# Dicio.net
KiCad netlist of a schematic drawn in EAGLE
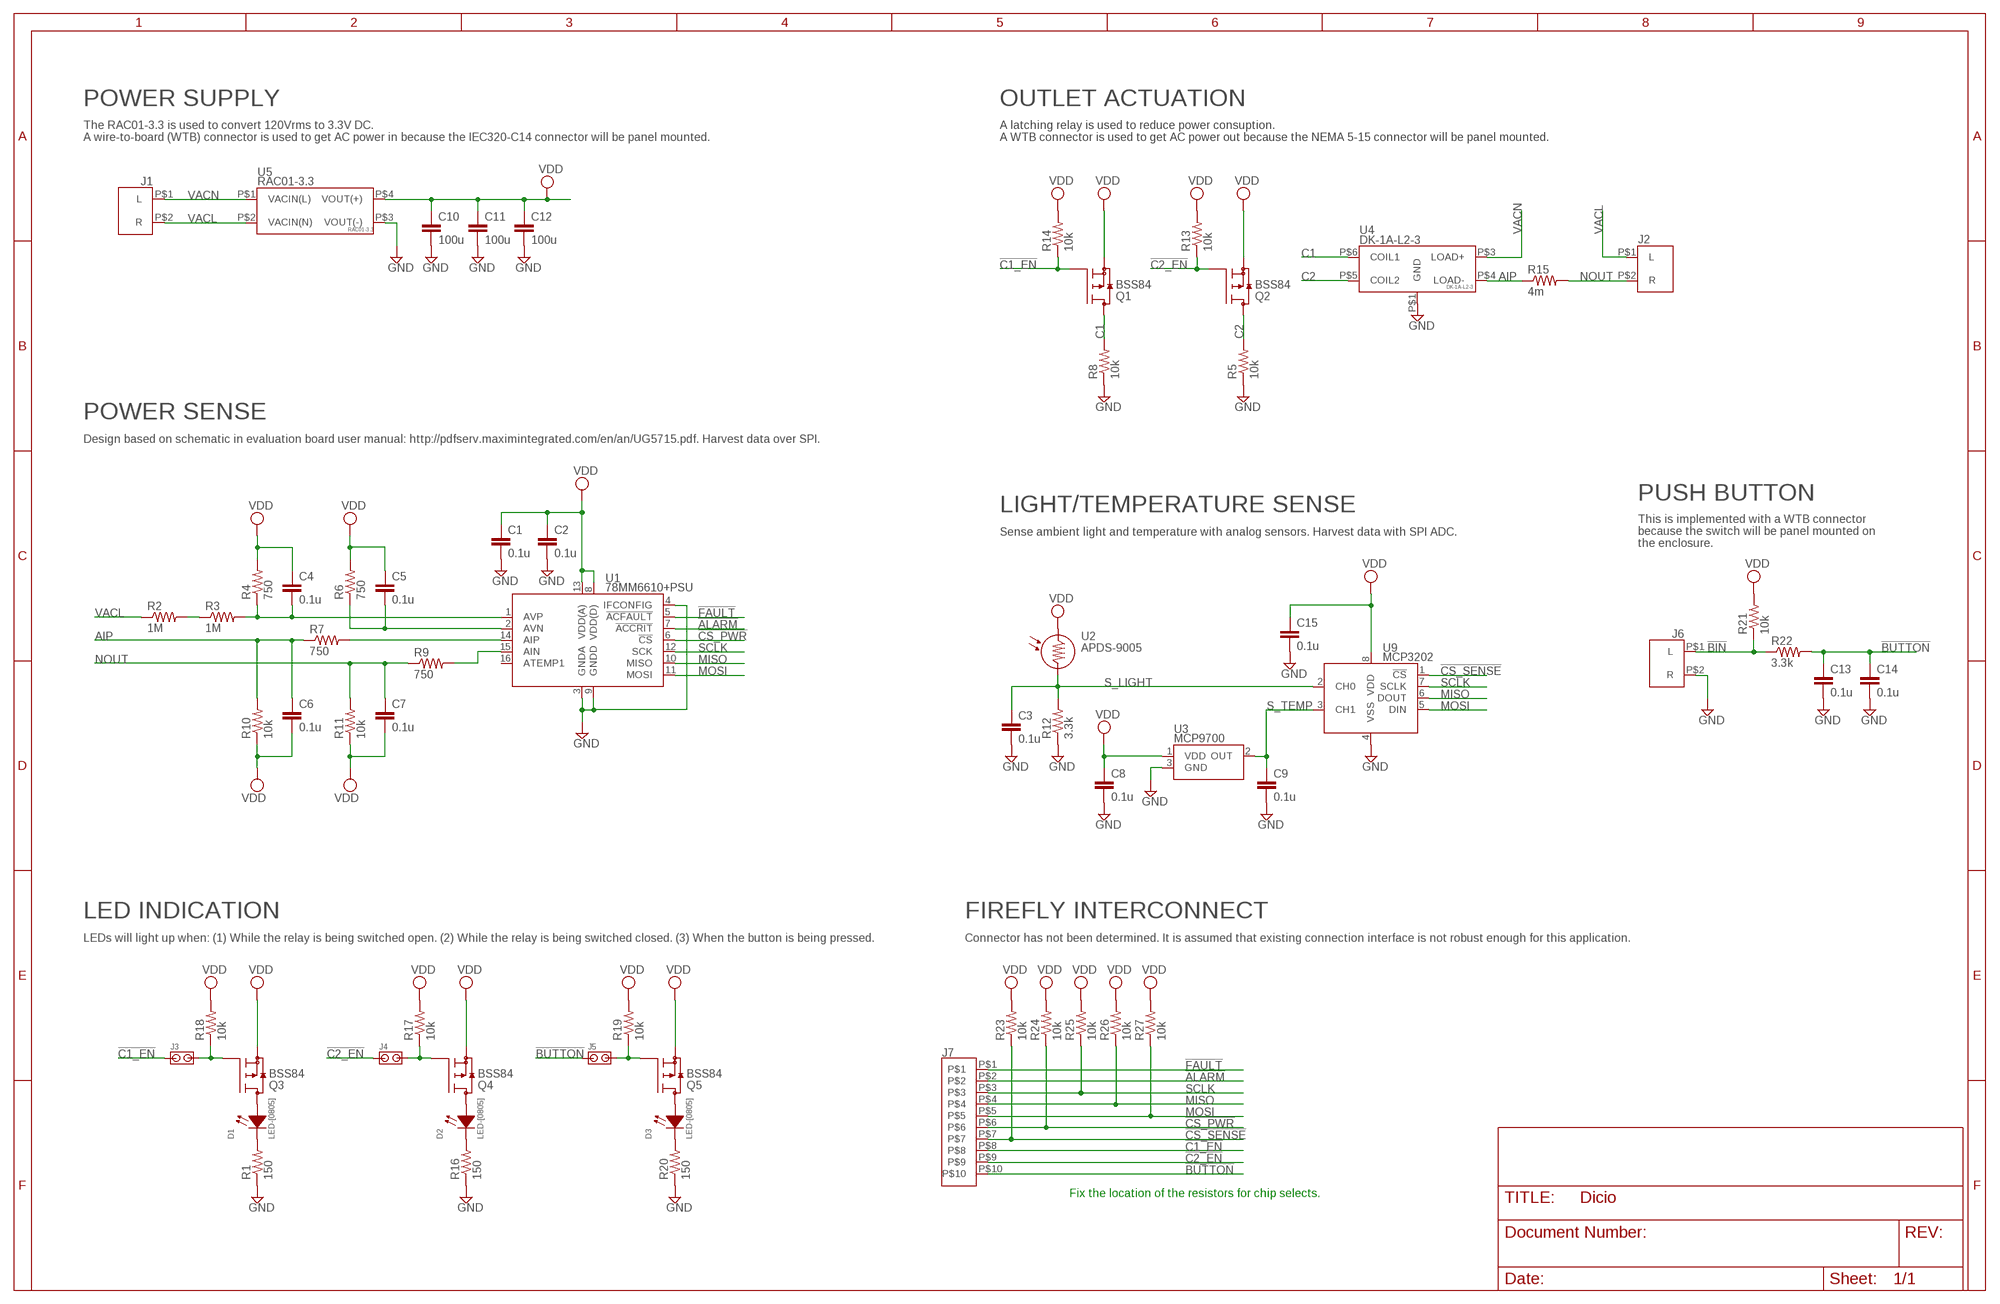
[diagram p0: schematic, sheet 1]

(export (version "E")
  (design (tool "Eeschema 10.0.6"))
  (components
    (comp (ref "C1")
      (value "0.1u")
      (footprint "eagle-import:C0805")
      (libsource (lib "eagle-import") (part "C-EUC0805"))
    )
    (comp (ref "C2")
      (value "0.1u")
      (footprint "eagle-import:C0805")
      (libsource (lib "eagle-import") (part "C-EUC0805"))
    )
    (comp (ref "C3")
      (value "0.1u")
      (footprint "eagle-import:C0805")
      (libsource (lib "eagle-import") (part "C-EUC0805"))
    )
    (comp (ref "C4")
      (value "0.1u")
      (footprint "eagle-import:C0805")
      (libsource (lib "eagle-import") (part "C-EUC0805"))
    )
    (comp (ref "C5")
      (value "0.1u")
      (footprint "eagle-import:C0805")
      (libsource (lib "eagle-import") (part "C-EUC0805"))
    )
    (comp (ref "C6")
      (value "0.1u")
      (footprint "eagle-import:C0805")
      (libsource (lib "eagle-import") (part "C-EUC0805"))
    )
    (comp (ref "C7")
      (value "0.1u")
      (footprint "eagle-import:C0805")
      (libsource (lib "eagle-import") (part "C-EUC0805"))
    )
    (comp (ref "C8")
      (value "0.1u")
      (footprint "eagle-import:C0805")
      (libsource (lib "eagle-import") (part "C-EUC0805"))
    )
    (comp (ref "C9")
      (value "0.1u")
      (footprint "eagle-import:C0805")
      (libsource (lib "eagle-import") (part "C-EUC0805"))
    )
    (comp (ref "C10")
      (value "100u")
      (footprint "eagle-import:C1206")
      (libsource (lib "eagle-import") (part "C-EUC1206"))
    )
    (comp (ref "C11")
      (value "100u")
      (footprint "eagle-import:C1206")
      (libsource (lib "eagle-import") (part "C-EUC1206"))
    )
    (comp (ref "C12")
      (value "100u")
      (footprint "eagle-import:C1206")
      (libsource (lib "eagle-import") (part "C-EUC1206"))
    )
    (comp (ref "C13")
      (value "0.1u")
      (footprint "eagle-import:C0805")
      (libsource (lib "eagle-import") (part "C-EUC0805"))
    )
    (comp (ref "C14")
      (value "0.1u")
      (footprint "eagle-import:C0805")
      (libsource (lib "eagle-import") (part "C-EUC0805"))
    )
    (comp (ref "C15")
      (value "0.1u")
      (footprint "eagle-import:C0805")
      (libsource (lib "eagle-import") (part "C-EUC0805"))
    )
    (comp (ref "D1")
      (value "LED-[0805]")
      (footprint "eagle-import:L0805")
      (libsource (lib "eagle-import") (part "LED-[0805]"))
    )
    (comp (ref "D2")
      (value "LED-[0805]")
      (footprint "eagle-import:L0805")
      (libsource (lib "eagle-import") (part "LED-[0805]"))
    )
    (comp (ref "D3")
      (value "LED-[0805]")
      (footprint "eagle-import:L0805")
      (libsource (lib "eagle-import") (part "LED-[0805]"))
    )
    (comp (ref "J1")
      (value "WTB-2")
      (footprint "eagle-import:[TERM][2][0.2]")
      (libsource (lib "eagle-import") (part "WTB-2"))
    )
    (comp (ref "J2")
      (value "WTB-2")
      (footprint "eagle-import:[TERM][2][0.2]")
      (libsource (lib "eagle-import") (part "WTB-2"))
    )
    (comp (ref "J3")
      (value "JMP2")
      (footprint "eagle-import:JMP2")
      (libsource (lib "eagle-import") (part "JMP2"))
    )
    (comp (ref "J4")
      (value "JMP2")
      (footprint "eagle-import:JMP2")
      (libsource (lib "eagle-import") (part "JMP2"))
    )
    (comp (ref "J5")
      (value "JMP2")
      (footprint "eagle-import:JMP2")
      (libsource (lib "eagle-import") (part "JMP2"))
    )
    (comp (ref "J6")
      (value "WTB-2")
      (footprint "eagle-import:[TERM][2][0.2]")
      (libsource (lib "eagle-import") (part "WTB-2"))
    )
    (comp (ref "J7")
      (value "TERM10")
      (footprint "eagle-import:TERM10")
      (libsource (lib "eagle-import") (part "TERM10"))
    )
    (comp (ref "Q1")
      (value "BSS84")
      (footprint "eagle-import:SOT23")
      (libsource (lib "eagle-import") (part "BSS84"))
    )
    (comp (ref "Q2")
      (value "BSS84")
      (footprint "eagle-import:SOT23")
      (libsource (lib "eagle-import") (part "BSS84"))
    )
    (comp (ref "Q3")
      (value "BSS84")
      (footprint "eagle-import:SOT23")
      (libsource (lib "eagle-import") (part "BSS84"))
    )
    (comp (ref "Q4")
      (value "BSS84")
      (footprint "eagle-import:SOT23")
      (libsource (lib "eagle-import") (part "BSS84"))
    )
    (comp (ref "Q5")
      (value "BSS84")
      (footprint "eagle-import:SOT23")
      (libsource (lib "eagle-import") (part "BSS84"))
    )
    (comp (ref "R1")
      (value "150")
      (footprint "eagle-import:R0805")
      (libsource (lib "eagle-import") (part "R-US_R0805"))
    )
    (comp (ref "R2")
      (value "1M")
      (footprint "eagle-import:R0805")
      (libsource (lib "eagle-import") (part "R-US_R0805"))
    )
    (comp (ref "R3")
      (value "1M")
      (footprint "eagle-import:R0805")
      (libsource (lib "eagle-import") (part "R-US_R0805"))
    )
    (comp (ref "R4")
      (value "750")
      (footprint "eagle-import:R0805")
      (libsource (lib "eagle-import") (part "R-US_R0805"))
    )
    (comp (ref "R5")
      (value "10k")
      (footprint "eagle-import:R0805")
      (libsource (lib "eagle-import") (part "R-US_R0805"))
    )
    (comp (ref "R6")
      (value "750")
      (footprint "eagle-import:R0805")
      (libsource (lib "eagle-import") (part "R-US_R0805"))
    )
    (comp (ref "R7")
      (value "750")
      (footprint "eagle-import:R0805")
      (libsource (lib "eagle-import") (part "R-US_R0805"))
    )
    (comp (ref "R8")
      (value "10k")
      (footprint "eagle-import:R0805")
      (libsource (lib "eagle-import") (part "R-US_R0805"))
    )
    (comp (ref "R9")
      (value "750")
      (footprint "eagle-import:R0805")
      (libsource (lib "eagle-import") (part "R-US_R0805"))
    )
    (comp (ref "R10")
      (value "10k")
      (footprint "eagle-import:R0805")
      (libsource (lib "eagle-import") (part "R-US_R0805"))
    )
    (comp (ref "R11")
      (value "10k")
      (footprint "eagle-import:R0805")
      (libsource (lib "eagle-import") (part "R-US_R0805"))
    )
    (comp (ref "R12")
      (value "3.3k")
      (footprint "eagle-import:R0805")
      (libsource (lib "eagle-import") (part "R-US_R0805"))
    )
    (comp (ref "R13")
      (value "10k")
      (footprint "eagle-import:R0805")
      (libsource (lib "eagle-import") (part "R-US_R0805"))
    )
    (comp (ref "R14")
      (value "10k")
      (footprint "eagle-import:R0805")
      (libsource (lib "eagle-import") (part "R-US_R0805"))
    )
    (comp (ref "R15")
      (value "4m")
      (footprint "eagle-import:R2512")
      (libsource (lib "eagle-import") (part "R-US_R2512"))
    )
    (comp (ref "R16")
      (value "150")
      (footprint "eagle-import:R0805")
      (libsource (lib "eagle-import") (part "R-US_R0805"))
    )
    (comp (ref "R17")
      (value "10k")
      (footprint "eagle-import:R0805")
      (libsource (lib "eagle-import") (part "R-US_R0805"))
    )
    (comp (ref "R18")
      (value "10k")
      (footprint "eagle-import:R0805")
      (libsource (lib "eagle-import") (part "R-US_R0805"))
    )
    (comp (ref "R19")
      (value "10k")
      (footprint "eagle-import:R0805")
      (libsource (lib "eagle-import") (part "R-US_R0805"))
    )
    (comp (ref "R20")
      (value "150")
      (footprint "eagle-import:R0805")
      (libsource (lib "eagle-import") (part "R-US_R0805"))
    )
    (comp (ref "R21")
      (value "10k")
      (footprint "eagle-import:R0805")
      (libsource (lib "eagle-import") (part "R-US_R0805"))
    )
    (comp (ref "R22")
      (value "3.3k")
      (footprint "eagle-import:R0805")
      (libsource (lib "eagle-import") (part "R-US_R0805"))
    )
    (comp (ref "R23")
      (value "10k")
      (footprint "eagle-import:R0805")
      (libsource (lib "eagle-import") (part "R-US_R0805"))
    )
    (comp (ref "R24")
      (value "10k")
      (footprint "eagle-import:R0805")
      (libsource (lib "eagle-import") (part "R-US_R0805"))
    )
    (comp (ref "R25")
      (value "10k")
      (footprint "eagle-import:R0805")
      (libsource (lib "eagle-import") (part "R-US_R0805"))
    )
    (comp (ref "R26")
      (value "10k")
      (footprint "eagle-import:R0805")
      (libsource (lib "eagle-import") (part "R-US_R0805"))
    )
    (comp (ref "R27")
      (value "10k")
      (footprint "eagle-import:R0805")
      (libsource (lib "eagle-import") (part "R-US_R0805"))
    )
    (comp (ref "U1")
      (value "78MM6610+PSU")
      (footprint "eagle-import:TSSOP16")
      (libsource (lib "eagle-import") (part "78MM6610+PSU"))
    )
    (comp (ref "U2")
      (value "APDS-9005")
      (footprint "eagle-import:APDS-9005")
      (libsource (lib "eagle-import") (part "APDS-9005"))
    )
    (comp (ref "U3")
      (value "MCP9700")
      (footprint "eagle-import:SOT23")
      (libsource (lib "eagle-import") (part "MCP9700"))
    )
    (comp (ref "U4")
      (value "DK-1A-L2-3")
      (footprint "eagle-import:DK-1A-L2-3")
      (libsource (lib "eagle-import") (part "DK-1A-L2-3"))
    )
    (comp (ref "U5")
      (value "RAC01-3.3")
      (footprint "eagle-import:RAC01-3.3")
      (libsource (lib "eagle-import") (part "RAC01-3.3"))
    )
    (comp (ref "U9")
      (value "MCP3202")
      (footprint "eagle-import:MSOP-8[MCP3202]")
      (libsource (lib "eagle-import") (part "MCP3202"))
    )
  )
  (nets
    (net (code "1") (name "/AIP") (class "Default")
      (node (ref "C6") (pin "1") (pinfunction "1_1") (pintype "passive"))
      (node (ref "R10") (pin "2") (pinfunction "2_2") (pintype "passive"))
      (node (ref "R15") (pin "1") (pinfunction "1_1") (pintype "passive"))
      (node (ref "R7") (pin "1") (pinfunction "1_1") (pintype "passive"))
      (node (ref "U4") (pin "P$4") (pinfunction "LOAD-_P$4") (pintype "bidirectional"))
    )
    (net (code "2") (name "/C1") (class "Default")
      (node (ref "Q1") (pin "3") (pinfunction "D_3") (pintype "bidirectional"))
      (node (ref "R8") (pin "2") (pinfunction "2_2") (pintype "passive"))
      (node (ref "U4") (pin "P$6") (pinfunction "COIL1_P$6") (pintype "bidirectional"))
    )
    (net (code "3") (name "/C2") (class "Default")
      (node (ref "Q2") (pin "3") (pinfunction "D_3") (pintype "bidirectional"))
      (node (ref "R5") (pin "2") (pinfunction "2_2") (pintype "passive"))
      (node (ref "U4") (pin "P$5") (pinfunction "COIL2_P$5") (pintype "bidirectional"))
    )
    (net (code "4") (name "/MISO") (class "Default")
      (node (ref "J7") (pin "P$4") (pinfunction "P$4_P$4") (pintype "bidirectional"))
      (node (ref "R26") (pin "1") (pinfunction "1_1") (pintype "passive"))
      (node (ref "U1") (pin "10") (pinfunction "MISO_10") (pintype "bidirectional"))
      (node (ref "U9") (pin "6") (pinfunction "DOUT_6") (pintype "bidirectional"))
    )
    (net (code "5") (name "/MOSI") (class "Default")
      (node (ref "J7") (pin "P$5") (pinfunction "P$5_P$5") (pintype "bidirectional"))
      (node (ref "R27") (pin "1") (pinfunction "1_1") (pintype "passive"))
      (node (ref "U1") (pin "11") (pinfunction "MOSI_11") (pintype "bidirectional"))
      (node (ref "U9") (pin "5") (pinfunction "DIN_5") (pintype "bidirectional"))
    )
    (net (code "6") (name "/NOUT") (class "Default")
      (node (ref "C7") (pin "1") (pinfunction "1_1") (pintype "passive"))
      (node (ref "J2") (pin "P$2") (pinfunction "R_P$2") (pintype "bidirectional"))
      (node (ref "R11") (pin "2") (pinfunction "2_2") (pintype "passive"))
      (node (ref "R15") (pin "2") (pinfunction "2_2") (pintype "passive"))
      (node (ref "R9") (pin "1") (pinfunction "1_1") (pintype "passive"))
    )
    (net (code "7") (name "/SCLK") (class "Default")
      (node (ref "J7") (pin "P$3") (pinfunction "P$3_P$3") (pintype "bidirectional"))
      (node (ref "R25") (pin "1") (pinfunction "1_1") (pintype "passive"))
      (node (ref "U1") (pin "12") (pinfunction "SCK_12") (pintype "bidirectional"))
      (node (ref "U9") (pin "7") (pinfunction "SCLK_7") (pintype "bidirectional"))
    )
    (net (code "8") (name "/S_LIGHT") (class "Default")
      (node (ref "C3") (pin "1") (pinfunction "1_1") (pintype "passive"))
      (node (ref "R12") (pin "2") (pinfunction "2_2") (pintype "passive"))
      (node (ref "U2") (pin "6") (pinfunction "ROUT_6") (pintype "bidirectional"))
      (node (ref "U9") (pin "2") (pinfunction "CH0_2") (pintype "bidirectional"))
    )
    (net (code "9") (name "/S_TEMP") (class "Default")
      (node (ref "C9") (pin "1") (pinfunction "1_1") (pintype "passive"))
      (node (ref "U3") (pin "2") (pinfunction "OUT_2") (pintype "bidirectional"))
      (node (ref "U9") (pin "3") (pinfunction "CH1_3") (pintype "bidirectional"))
    )
    (net (code "10") (name "/VACL") (class "Default")
      (node (ref "J1") (pin "P$2") (pinfunction "R_P$2") (pintype "bidirectional"))
      (node (ref "J2") (pin "P$1") (pinfunction "L_P$1") (pintype "bidirectional"))
      (node (ref "R2") (pin "1") (pinfunction "1_1") (pintype "passive"))
      (node (ref "U5") (pin "P$2") (pinfunction "VACIN(N)_P$2") (pintype "bidirectional"))
    )
    (net (code "11") (name "/VACN") (class "Default")
      (node (ref "J1") (pin "P$1") (pinfunction "L_P$1") (pintype "bidirectional"))
      (node (ref "U4") (pin "P$3") (pinfunction "LOAD+_P$3") (pintype "bidirectional"))
      (node (ref "U5") (pin "P$1") (pinfunction "VACIN(L)_P$1") (pintype "bidirectional"))
    )
    (net (code "12") (name "/~{ALARM}") (class "Default")
      (node (ref "J7") (pin "P$2") (pinfunction "P$2_P$2") (pintype "bidirectional"))
      (node (ref "U1") (pin "7") (pinfunction "~{ACCRIT}_7") (pintype "bidirectional"))
    )
    (net (code "13") (name "/~{BIN}") (class "Default")
      (node (ref "J6") (pin "P$1") (pinfunction "L_P$1") (pintype "bidirectional"))
      (node (ref "R21") (pin "1") (pinfunction "1_1") (pintype "passive"))
      (node (ref "R22") (pin "1") (pinfunction "1_1") (pintype "passive"))
    )
    (net (code "14") (name "/~{BUTTON}") (class "Default")
      (node (ref "C13") (pin "1") (pinfunction "1_1") (pintype "passive"))
      (node (ref "C14") (pin "1") (pinfunction "1_1") (pintype "passive"))
      (node (ref "J5") (pin "P$2") (pinfunction "P$2_P$2") (pintype "bidirectional"))
      (node (ref "J7") (pin "P$10") (pinfunction "P$10_P$10") (pintype "bidirectional"))
      (node (ref "R22") (pin "2") (pinfunction "2_2") (pintype "passive"))
    )
    (net (code "15") (name "/~{C1_EN}") (class "Default")
      (node (ref "J3") (pin "P$2") (pinfunction "P$2_P$2") (pintype "bidirectional"))
      (node (ref "J7") (pin "P$8") (pinfunction "P$8_P$8") (pintype "bidirectional"))
      (node (ref "Q1") (pin "1") (pinfunction "G_1") (pintype "bidirectional"))
      (node (ref "R14") (pin "1") (pinfunction "1_1") (pintype "passive"))
    )
    (net (code "16") (name "/~{C2_EN}") (class "Default")
      (node (ref "J4") (pin "P$2") (pinfunction "P$2_P$2") (pintype "bidirectional"))
      (node (ref "J7") (pin "P$9") (pinfunction "P$9_P$9") (pintype "bidirectional"))
      (node (ref "Q2") (pin "1") (pinfunction "G_1") (pintype "bidirectional"))
      (node (ref "R13") (pin "1") (pinfunction "1_1") (pintype "passive"))
    )
    (net (code "17") (name "/~{CS_PWR}") (class "Default")
      (node (ref "J7") (pin "P$6") (pinfunction "P$6_P$6") (pintype "bidirectional"))
      (node (ref "R24") (pin "1") (pinfunction "1_1") (pintype "passive"))
      (node (ref "U1") (pin "6") (pinfunction "~{CS}_6") (pintype "bidirectional"))
    )
    (net (code "18") (name "/~{CS_SENSE}") (class "Default")
      (node (ref "J7") (pin "P$7") (pinfunction "P$7_P$7") (pintype "bidirectional"))
      (node (ref "R23") (pin "1") (pinfunction "1_1") (pintype "passive"))
      (node (ref "U9") (pin "1") (pinfunction "~{CS}_1") (pintype "bidirectional"))
    )
    (net (code "19") (name "/~{FAULT}") (class "Default")
      (node (ref "J7") (pin "P$1") (pinfunction "P$1_P$1") (pintype "bidirectional"))
      (node (ref "U1") (pin "5") (pinfunction "~{ACFAULT}_5") (pintype "bidirectional"))
    )
    (net (code "20") (name "GND") (class "Default")
      (node (ref "C1") (pin "2") (pinfunction "2_2") (pintype "passive"))
      (node (ref "C10") (pin "2") (pinfunction "2_2") (pintype "passive"))
      (node (ref "C11") (pin "2") (pinfunction "2_2") (pintype "passive"))
      (node (ref "C12") (pin "2") (pinfunction "2_2") (pintype "passive"))
      (node (ref "C13") (pin "2") (pinfunction "2_2") (pintype "passive"))
      (node (ref "C14") (pin "2") (pinfunction "2_2") (pintype "passive"))
      (node (ref "C15") (pin "2") (pinfunction "2_2") (pintype "passive"))
      (node (ref "C2") (pin "2") (pinfunction "2_2") (pintype "passive"))
      (node (ref "C3") (pin "2") (pinfunction "2_2") (pintype "passive"))
      (node (ref "C8") (pin "2") (pinfunction "2_2") (pintype "passive"))
      (node (ref "C9") (pin "2") (pinfunction "2_2") (pintype "passive"))
      (node (ref "J6") (pin "P$2") (pinfunction "R_P$2") (pintype "bidirectional"))
      (node (ref "R1") (pin "1") (pinfunction "1_1") (pintype "passive"))
      (node (ref "R12") (pin "1") (pinfunction "1_1") (pintype "passive"))
      (node (ref "R16") (pin "1") (pinfunction "1_1") (pintype "passive"))
      (node (ref "R20") (pin "1") (pinfunction "1_1") (pintype "passive"))
      (node (ref "R5") (pin "1") (pinfunction "1_1") (pintype "passive"))
      (node (ref "R8") (pin "1") (pinfunction "1_1") (pintype "passive"))
      (node (ref "U1") (pin "3") (pinfunction "GNDA_3") (pintype "bidirectional"))
      (node (ref "U1") (pin "4") (pinfunction "IFCONFIG_4") (pintype "bidirectional"))
      (node (ref "U1") (pin "9") (pinfunction "GNDD_9") (pintype "bidirectional"))
      (node (ref "U3") (pin "3") (pinfunction "GND_3") (pintype "bidirectional"))
      (node (ref "U4") (pin "P$1") (pinfunction "GND_P$1") (pintype "bidirectional"))
      (node (ref "U5") (pin "P$3") (pinfunction "VOUT(-)_P$3") (pintype "bidirectional"))
      (node (ref "U9") (pin "4") (pinfunction "VSS_4") (pintype "bidirectional"))
    )
    (net (code "21") (name "Net-(D1-A)") (class "Default")
      (node (ref "D1") (pin "1") (pinfunction "A_1") (pintype "bidirectional"))
      (node (ref "Q3") (pin "3") (pinfunction "D_3") (pintype "bidirectional"))
    )
    (net (code "22") (name "Net-(D1-C)") (class "Default")
      (node (ref "D1") (pin "2") (pinfunction "C_2") (pintype "bidirectional"))
      (node (ref "R1") (pin "2") (pinfunction "2_2") (pintype "passive"))
    )
    (net (code "23") (name "Net-(D2-A)") (class "Default")
      (node (ref "D2") (pin "1") (pinfunction "A_1") (pintype "bidirectional"))
      (node (ref "Q4") (pin "3") (pinfunction "D_3") (pintype "bidirectional"))
    )
    (net (code "24") (name "Net-(D2-C)") (class "Default")
      (node (ref "D2") (pin "2") (pinfunction "C_2") (pintype "bidirectional"))
      (node (ref "R16") (pin "2") (pinfunction "2_2") (pintype "passive"))
    )
    (net (code "25") (name "Net-(D3-A)") (class "Default")
      (node (ref "D3") (pin "1") (pinfunction "A_1") (pintype "bidirectional"))
      (node (ref "Q5") (pin "3") (pinfunction "D_3") (pintype "bidirectional"))
    )
    (net (code "26") (name "Net-(D3-C)") (class "Default")
      (node (ref "D3") (pin "2") (pinfunction "C_2") (pintype "bidirectional"))
      (node (ref "R20") (pin "2") (pinfunction "2_2") (pintype "passive"))
    )
    (net (code "27") (name "Net-(J3-1)") (class "Default")
      (node (ref "J3") (pin "P$1") (pinfunction "1_P$1") (pintype "bidirectional"))
      (node (ref "Q3") (pin "1") (pinfunction "G_1") (pintype "bidirectional"))
      (node (ref "R18") (pin "1") (pinfunction "1_1") (pintype "passive"))
    )
    (net (code "28") (name "Net-(J4-1)") (class "Default")
      (node (ref "J4") (pin "P$1") (pinfunction "1_P$1") (pintype "bidirectional"))
      (node (ref "Q4") (pin "1") (pinfunction "G_1") (pintype "bidirectional"))
      (node (ref "R17") (pin "1") (pinfunction "1_1") (pintype "passive"))
    )
    (net (code "29") (name "Net-(J5-1)") (class "Default")
      (node (ref "J5") (pin "P$1") (pinfunction "1_P$1") (pintype "bidirectional"))
      (node (ref "Q5") (pin "1") (pinfunction "G_1") (pintype "bidirectional"))
      (node (ref "R19") (pin "1") (pinfunction "1_1") (pintype "passive"))
    )
    (net (code "30") (name "Net-(R2-Pad2)") (class "Default")
      (node (ref "R2") (pin "2") (pinfunction "2_2") (pintype "passive"))
      (node (ref "R3") (pin "1") (pinfunction "1_1") (pintype "passive"))
    )
    (net (code "31") (name "Net-(U1-AIN)") (class "Default")
      (node (ref "R9") (pin "2") (pinfunction "2_2") (pintype "passive"))
      (node (ref "U1") (pin "15") (pinfunction "AIN_15") (pintype "bidirectional"))
    )
    (net (code "32") (name "Net-(U1-AIP)") (class "Default")
      (node (ref "R7") (pin "2") (pinfunction "2_2") (pintype "passive"))
      (node (ref "U1") (pin "14") (pinfunction "AIP_14") (pintype "bidirectional"))
    )
    (net (code "33") (name "Net-(U1-AVN)") (class "Default")
      (node (ref "C5") (pin "2") (pinfunction "2_2") (pintype "passive"))
      (node (ref "R6") (pin "1") (pinfunction "1_1") (pintype "passive"))
      (node (ref "U1") (pin "2") (pinfunction "AVN_2") (pintype "bidirectional"))
    )
    (net (code "34") (name "Net-(U1-AVP)") (class "Default")
      (node (ref "C4") (pin "2") (pinfunction "2_2") (pintype "passive"))
      (node (ref "R3") (pin "2") (pinfunction "2_2") (pintype "passive"))
      (node (ref "R4") (pin "1") (pinfunction "1_1") (pintype "passive"))
      (node (ref "U1") (pin "1") (pinfunction "AVP_1") (pintype "bidirectional"))
    )
    (net (code "35") (name "VDD") (class "Default")
      (node (ref "C1") (pin "1") (pinfunction "1_1") (pintype "passive"))
      (node (ref "C10") (pin "1") (pinfunction "1_1") (pintype "passive"))
      (node (ref "C11") (pin "1") (pinfunction "1_1") (pintype "passive"))
      (node (ref "C12") (pin "1") (pinfunction "1_1") (pintype "passive"))
      (node (ref "C15") (pin "1") (pinfunction "1_1") (pintype "passive"))
      (node (ref "C2") (pin "1") (pinfunction "1_1") (pintype "passive"))
      (node (ref "C4") (pin "1") (pinfunction "1_1") (pintype "passive"))
      (node (ref "C5") (pin "1") (pinfunction "1_1") (pintype "passive"))
      (node (ref "C6") (pin "2") (pinfunction "2_2") (pintype "passive"))
      (node (ref "C7") (pin "2") (pinfunction "2_2") (pintype "passive"))
      (node (ref "C8") (pin "1") (pinfunction "1_1") (pintype "passive"))
      (node (ref "Q1") (pin "2") (pinfunction "S_2") (pintype "bidirectional"))
      (node (ref "Q2") (pin "2") (pinfunction "S_2") (pintype "bidirectional"))
      (node (ref "Q3") (pin "2") (pinfunction "S_2") (pintype "bidirectional"))
      (node (ref "Q4") (pin "2") (pinfunction "S_2") (pintype "bidirectional"))
      (node (ref "Q5") (pin "2") (pinfunction "S_2") (pintype "bidirectional"))
      (node (ref "R10") (pin "1") (pinfunction "1_1") (pintype "passive"))
      (node (ref "R11") (pin "1") (pinfunction "1_1") (pintype "passive"))
      (node (ref "R13") (pin "2") (pinfunction "2_2") (pintype "passive"))
      (node (ref "R14") (pin "2") (pinfunction "2_2") (pintype "passive"))
      (node (ref "R17") (pin "2") (pinfunction "2_2") (pintype "passive"))
      (node (ref "R18") (pin "2") (pinfunction "2_2") (pintype "passive"))
      (node (ref "R19") (pin "2") (pinfunction "2_2") (pintype "passive"))
      (node (ref "R21") (pin "2") (pinfunction "2_2") (pintype "passive"))
      (node (ref "R23") (pin "2") (pinfunction "2_2") (pintype "passive"))
      (node (ref "R24") (pin "2") (pinfunction "2_2") (pintype "passive"))
      (node (ref "R25") (pin "2") (pinfunction "2_2") (pintype "passive"))
      (node (ref "R26") (pin "2") (pinfunction "2_2") (pintype "passive"))
      (node (ref "R27") (pin "2") (pinfunction "2_2") (pintype "passive"))
      (node (ref "R4") (pin "2") (pinfunction "2_2") (pintype "passive"))
      (node (ref "R6") (pin "2") (pinfunction "2_2") (pintype "passive"))
      (node (ref "U1") (pin "13") (pinfunction "VDD(A)_13") (pintype "bidirectional"))
      (node (ref "U1") (pin "8") (pinfunction "VDD(D)_8") (pintype "bidirectional"))
      (node (ref "U2") (pin "1") (pinfunction "VDD_1") (pintype "bidirectional"))
      (node (ref "U3") (pin "1") (pinfunction "VDD_1") (pintype "bidirectional"))
      (node (ref "U5") (pin "P$4") (pinfunction "VOUT(+)_P$4") (pintype "bidirectional"))
      (node (ref "U9") (pin "8") (pinfunction "VDD_8") (pintype "bidirectional"))
    )
    (net (code "36") (name "unconnected-(U1-ATEMP1-Pad16)") (class "Default")
      (node (ref "U1") (pin "16") (pinfunction "ATEMP1_16") (pintype "bidirectional"))
    )
    (net (code "37") (name "unconnected-(U2-NC1-Pad2)") (class "Default")
      (node (ref "U2") (pin "2") (pinfunction "NC1_2") (pintype "bidirectional"))
    )
    (net (code "38") (name "unconnected-(U2-NC2-Pad3)") (class "Default")
      (node (ref "U2") (pin "3") (pinfunction "NC2_3") (pintype "bidirectional"))
    )
    (net (code "39") (name "unconnected-(U2-NC3-Pad4)") (class "Default")
      (node (ref "U2") (pin "4") (pinfunction "NC3_4") (pintype "bidirectional"))
    )
    (net (code "40") (name "unconnected-(U2-NC4-Pad5)") (class "Default")
      (node (ref "U2") (pin "5") (pinfunction "NC4_5") (pintype "bidirectional"))
    )
  )
)
